# ADCMultiplexerFrontEnd.net
KiCad netlist of a schematic drawn in Altium Designer
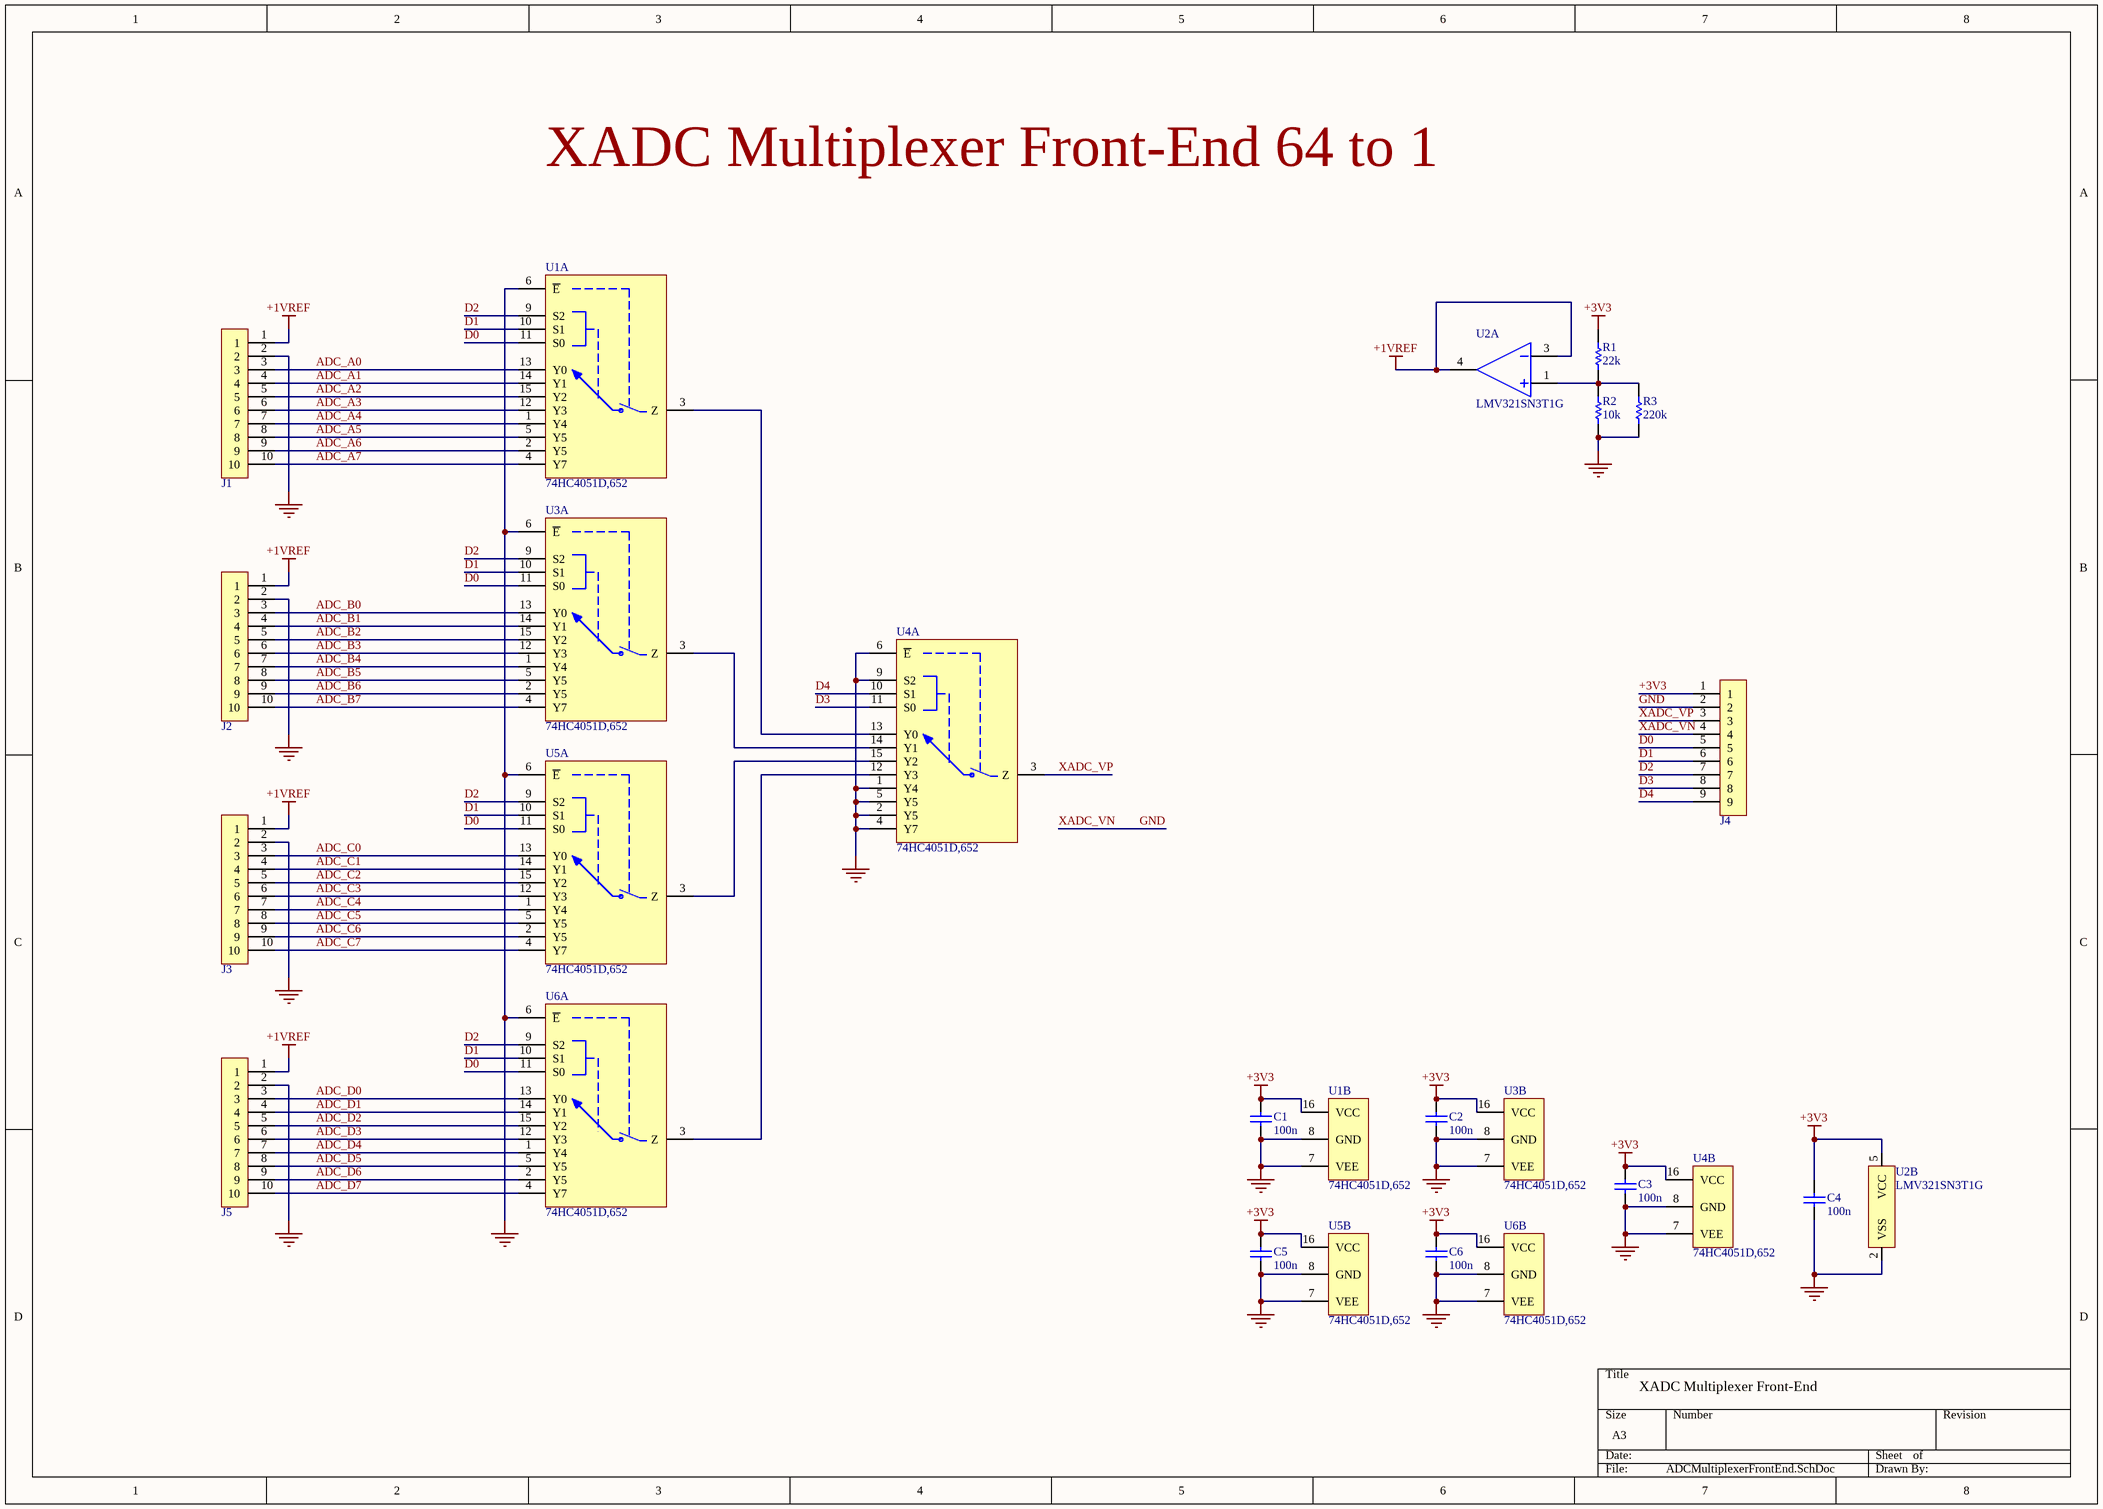
[diagram p0: ADCMultiplexerFrontEnd.SchDoc]

(export (version "E")
  (design (tool "Eeschema 10.0.6"))
  (components
    (comp (ref "C1")
      (value "100n")
      (footprint "C0603")
      (libsource (lib "UserLibrary") (part "C0603KC0G100V104"))
    )
    (comp (ref "C2")
      (value "100n")
      (footprint "C0603")
      (libsource (lib "UserLibrary") (part "C0603KC0G100V104"))
    )
    (comp (ref "C3")
      (value "100n")
      (footprint "C0603")
      (libsource (lib "UserLibrary") (part "C0603KC0G100V104"))
    )
    (comp (ref "C4")
      (value "100n")
      (footprint "C0603")
      (libsource (lib "UserLibrary") (part "C0603KC0G100V104"))
    )
    (comp (ref "C5")
      (value "100n")
      (footprint "C0603")
      (libsource (lib "UserLibrary") (part "C0603KC0G100V104"))
    )
    (comp (ref "C6")
      (value "100n")
      (footprint "C0603")
      (libsource (lib "UserLibrary") (part "C0603KC0G100V104"))
    )
    (comp (ref "J1")
      (value "HDR M 1x8 2.54MM")
      (footprint "HDR M 1x10 2.54MM")
      (libsource (lib "UserLibrary") (part "HDR M 1x10 2.54MM"))
    )
    (comp (ref "J2")
      (value "HDR M 1x8 2.54MM")
      (footprint "HDR M 1x10 2.54MM")
      (libsource (lib "UserLibrary") (part "HDR M 1x10 2.54MM"))
    )
    (comp (ref "J3")
      (value "HDR M 1x8 2.54MM")
      (footprint "HDR M 1x10 2.54MM")
      (libsource (lib "UserLibrary") (part "HDR M 1x10 2.54MM"))
    )
    (comp (ref "J4")
      (value "HDR M 1x8 2.54MM")
      (footprint "HDR M 1x9 2.54MM")
      (libsource (lib "UserLibrary") (part "HDR M 1x9 2.54MM"))
    )
    (comp (ref "J5")
      (value "HDR M 1x8 2.54MM")
      (footprint "HDR M 1x10 2.54MM")
      (libsource (lib "UserLibrary") (part "HDR M 1x10 2.54MM"))
    )
    (comp (ref "R1") (value "22k") (footprint "R0805") (libsource (lib "UserLibrary") (part "R0805F22K")))
    (comp (ref "R2") (value "10k") (footprint "R0805") (libsource (lib "UserLibrary") (part "R0805F10K")))
    (comp (ref "R3") (value "220k") (footprint "R0805") (libsource (lib "UserLibrary") (part "R0805F220K")))
    (comp (ref "U1")
      (value "74HC4051D,652")
      (footprint "SOIC16")
      (description "IC MUX/DEMUX 8X1 16SOIC")
      (fields (field (name "MANUFACTURER") "Nexperia"))
      (libsource (lib "UserLibrary") (part "74HC4051D,652"))
    )
    (comp (ref "U2")
      (value "LMV321SN3T1G")
      (footprint "TSOP5")
      (description "ON SEMICONDUCTOR - LMV321SN3T1G - OP-AMP, SINGLE, 1MHZ, 1V/US, TSOP-5")
      (fields (field (name "MANUFACTURER") "ON Semiconductor"))
      (libsource (lib "") (part "LMV321SN3T1G_1"))
    )
    (comp (ref "U3")
      (value "74HC4051D,652")
      (footprint "SOIC16")
      (description "IC MUX/DEMUX 8X1 16SOIC")
      (fields (field (name "MANUFACTURER") "Nexperia"))
      (libsource (lib "UserLibrary") (part "74HC4051D,652"))
    )
    (comp (ref "U4")
      (value "74HC4051D,652")
      (footprint "SOIC16")
      (description "IC MUX/DEMUX 8X1 16SOIC")
      (fields (field (name "MANUFACTURER") "Nexperia"))
      (libsource (lib "UserLibrary") (part "74HC4051D,652"))
    )
    (comp (ref "U5")
      (value "74HC4051D,652")
      (footprint "SOIC16")
      (description "IC MUX/DEMUX 8X1 16SOIC")
      (fields (field (name "MANUFACTURER") "Nexperia"))
      (libsource (lib "UserLibrary") (part "74HC4051D,652"))
    )
    (comp (ref "U6")
      (value "74HC4051D,652")
      (footprint "SOIC16")
      (description "IC MUX/DEMUX 8X1 16SOIC")
      (fields (field (name "MANUFACTURER") "Nexperia"))
      (libsource (lib "UserLibrary") (part "74HC4051D,652"))
    )
  )
  (nets
    (net (code "1") (name "+1VREF") (class "Default")
      (node (ref "J1") (pin "1") (pinfunction "1_1") (pintype "passive"))
      (node (ref "J2") (pin "1") (pinfunction "1_1") (pintype "passive"))
      (node (ref "J3") (pin "1") (pinfunction "1_1") (pintype "passive"))
      (node (ref "J5") (pin "1") (pinfunction "1_1") (pintype "passive"))
      (node (ref "U2") (pin "3") (pinfunction "3_3") (pintype "passive"))
      (node (ref "U2") (pin "4") (pinfunction "4_4") (pintype "passive"))
    )
    (net (code "2") (name "+3V3") (class "Default")
      (node (ref "C1") (pin "2") (pinfunction "2_2") (pintype "passive"))
      (node (ref "C2") (pin "2") (pinfunction "2_2") (pintype "passive"))
      (node (ref "C3") (pin "2") (pinfunction "2_2") (pintype "passive"))
      (node (ref "C4") (pin "2") (pinfunction "2_2") (pintype "passive"))
      (node (ref "C5") (pin "2") (pinfunction "2_2") (pintype "passive"))
      (node (ref "C6") (pin "2") (pinfunction "2_2") (pintype "passive"))
      (node (ref "J4") (pin "1") (pinfunction "1_1") (pintype "passive"))
      (node (ref "R1") (pin "2") (pinfunction "2_2") (pintype "passive"))
      (node (ref "U1") (pin "16") (pinfunction "VCC_16") (pintype "passive"))
      (node (ref "U2") (pin "5") (pinfunction "VCC_5") (pintype "passive"))
      (node (ref "U3") (pin "16") (pinfunction "VCC_16") (pintype "passive"))
      (node (ref "U4") (pin "16") (pinfunction "VCC_16") (pintype "passive"))
      (node (ref "U5") (pin "16") (pinfunction "VCC_16") (pintype "passive"))
      (node (ref "U6") (pin "16") (pinfunction "VCC_16") (pintype "passive"))
    )
    (net (code "3") (name "/ADC_A0") (class "Default")
      (node (ref "J1") (pin "3") (pinfunction "3_3") (pintype "passive"))
      (node (ref "U1") (pin "13") (pinfunction "Y0_13") (pintype "passive"))
    )
    (net (code "4") (name "/ADC_A1") (class "Default")
      (node (ref "J1") (pin "4") (pinfunction "4_4") (pintype "passive"))
      (node (ref "U1") (pin "14") (pinfunction "Y1_14") (pintype "passive"))
    )
    (net (code "5") (name "/ADC_A2") (class "Default")
      (node (ref "J1") (pin "5") (pinfunction "5_5") (pintype "passive"))
      (node (ref "U1") (pin "15") (pinfunction "Y2_15") (pintype "passive"))
    )
    (net (code "6") (name "/ADC_A3") (class "Default")
      (node (ref "J1") (pin "6") (pinfunction "6_6") (pintype "passive"))
      (node (ref "U1") (pin "12") (pinfunction "Y3_12") (pintype "passive"))
    )
    (net (code "7") (name "/ADC_A4") (class "Default")
      (node (ref "J1") (pin "7") (pinfunction "7_7") (pintype "passive"))
      (node (ref "U1") (pin "1") (pinfunction "Y4_1") (pintype "passive"))
    )
    (net (code "8") (name "/ADC_A5") (class "Default")
      (node (ref "J1") (pin "8") (pinfunction "8_8") (pintype "passive"))
      (node (ref "U1") (pin "5") (pinfunction "Y5_5") (pintype "passive"))
    )
    (net (code "9") (name "/ADC_A6") (class "Default")
      (node (ref "J1") (pin "9") (pinfunction "9_9") (pintype "passive"))
      (node (ref "U1") (pin "2") (pinfunction "Y5_2") (pintype "passive"))
    )
    (net (code "10") (name "/ADC_A7") (class "Default")
      (node (ref "J1") (pin "10") (pinfunction "10_10") (pintype "passive"))
      (node (ref "U1") (pin "4") (pinfunction "Y7_4") (pintype "passive"))
    )
    (net (code "11") (name "/ADC_B0") (class "Default")
      (node (ref "J2") (pin "3") (pinfunction "3_3") (pintype "passive"))
      (node (ref "U3") (pin "13") (pinfunction "Y0_13") (pintype "passive"))
    )
    (net (code "12") (name "/ADC_B1") (class "Default")
      (node (ref "J2") (pin "4") (pinfunction "4_4") (pintype "passive"))
      (node (ref "U3") (pin "14") (pinfunction "Y1_14") (pintype "passive"))
    )
    (net (code "13") (name "/ADC_B2") (class "Default")
      (node (ref "J2") (pin "5") (pinfunction "5_5") (pintype "passive"))
      (node (ref "U3") (pin "15") (pinfunction "Y2_15") (pintype "passive"))
    )
    (net (code "14") (name "/ADC_B3") (class "Default")
      (node (ref "J2") (pin "6") (pinfunction "6_6") (pintype "passive"))
      (node (ref "U3") (pin "12") (pinfunction "Y3_12") (pintype "passive"))
    )
    (net (code "15") (name "/ADC_B4") (class "Default")
      (node (ref "J2") (pin "7") (pinfunction "7_7") (pintype "passive"))
      (node (ref "U3") (pin "1") (pinfunction "Y4_1") (pintype "passive"))
    )
    (net (code "16") (name "/ADC_B5") (class "Default")
      (node (ref "J2") (pin "8") (pinfunction "8_8") (pintype "passive"))
      (node (ref "U3") (pin "5") (pinfunction "Y5_5") (pintype "passive"))
    )
    (net (code "17") (name "/ADC_B6") (class "Default")
      (node (ref "J2") (pin "9") (pinfunction "9_9") (pintype "passive"))
      (node (ref "U3") (pin "2") (pinfunction "Y5_2") (pintype "passive"))
    )
    (net (code "18") (name "/ADC_B7") (class "Default")
      (node (ref "J2") (pin "10") (pinfunction "10_10") (pintype "passive"))
      (node (ref "U3") (pin "4") (pinfunction "Y7_4") (pintype "passive"))
    )
    (net (code "19") (name "/ADC_C0") (class "Default")
      (node (ref "J3") (pin "3") (pinfunction "3_3") (pintype "passive"))
      (node (ref "U5") (pin "13") (pinfunction "Y0_13") (pintype "passive"))
    )
    (net (code "20") (name "/ADC_C1") (class "Default")
      (node (ref "J3") (pin "4") (pinfunction "4_4") (pintype "passive"))
      (node (ref "U5") (pin "14") (pinfunction "Y1_14") (pintype "passive"))
    )
    (net (code "21") (name "/ADC_C2") (class "Default")
      (node (ref "J3") (pin "5") (pinfunction "5_5") (pintype "passive"))
      (node (ref "U5") (pin "15") (pinfunction "Y2_15") (pintype "passive"))
    )
    (net (code "22") (name "/ADC_C3") (class "Default")
      (node (ref "J3") (pin "6") (pinfunction "6_6") (pintype "passive"))
      (node (ref "U5") (pin "12") (pinfunction "Y3_12") (pintype "passive"))
    )
    (net (code "23") (name "/ADC_C4") (class "Default")
      (node (ref "J3") (pin "7") (pinfunction "7_7") (pintype "passive"))
      (node (ref "U5") (pin "1") (pinfunction "Y4_1") (pintype "passive"))
    )
    (net (code "24") (name "/ADC_C5") (class "Default")
      (node (ref "J3") (pin "8") (pinfunction "8_8") (pintype "passive"))
      (node (ref "U5") (pin "5") (pinfunction "Y5_5") (pintype "passive"))
    )
    (net (code "25") (name "/ADC_C6") (class "Default")
      (node (ref "J3") (pin "9") (pinfunction "9_9") (pintype "passive"))
      (node (ref "U5") (pin "2") (pinfunction "Y5_2") (pintype "passive"))
    )
    (net (code "26") (name "/ADC_C7") (class "Default")
      (node (ref "J3") (pin "10") (pinfunction "10_10") (pintype "passive"))
      (node (ref "U5") (pin "4") (pinfunction "Y7_4") (pintype "passive"))
    )
    (net (code "27") (name "/ADC_D0") (class "Default")
      (node (ref "J5") (pin "3") (pinfunction "3_3") (pintype "passive"))
      (node (ref "U6") (pin "13") (pinfunction "Y0_13") (pintype "passive"))
    )
    (net (code "28") (name "/ADC_D1") (class "Default")
      (node (ref "J5") (pin "4") (pinfunction "4_4") (pintype "passive"))
      (node (ref "U6") (pin "14") (pinfunction "Y1_14") (pintype "passive"))
    )
    (net (code "29") (name "/ADC_D2") (class "Default")
      (node (ref "J5") (pin "5") (pinfunction "5_5") (pintype "passive"))
      (node (ref "U6") (pin "15") (pinfunction "Y2_15") (pintype "passive"))
    )
    (net (code "30") (name "/ADC_D3") (class "Default")
      (node (ref "J5") (pin "6") (pinfunction "6_6") (pintype "passive"))
      (node (ref "U6") (pin "12") (pinfunction "Y3_12") (pintype "passive"))
    )
    (net (code "31") (name "/ADC_D4") (class "Default")
      (node (ref "J5") (pin "7") (pinfunction "7_7") (pintype "passive"))
      (node (ref "U6") (pin "1") (pinfunction "Y4_1") (pintype "passive"))
    )
    (net (code "32") (name "/ADC_D5") (class "Default")
      (node (ref "J5") (pin "8") (pinfunction "8_8") (pintype "passive"))
      (node (ref "U6") (pin "5") (pinfunction "Y5_5") (pintype "passive"))
    )
    (net (code "33") (name "/ADC_D6") (class "Default")
      (node (ref "J5") (pin "9") (pinfunction "9_9") (pintype "passive"))
      (node (ref "U6") (pin "2") (pinfunction "Y5_2") (pintype "passive"))
    )
    (net (code "34") (name "/ADC_D7") (class "Default")
      (node (ref "J5") (pin "10") (pinfunction "10_10") (pintype "passive"))
      (node (ref "U6") (pin "4") (pinfunction "Y7_4") (pintype "passive"))
    )
    (net (code "35") (name "/D0") (class "Default")
      (node (ref "J4") (pin "5") (pinfunction "5_5") (pintype "passive"))
      (node (ref "U1") (pin "11") (pinfunction "S0_11") (pintype "passive"))
      (node (ref "U3") (pin "11") (pinfunction "S0_11") (pintype "passive"))
      (node (ref "U5") (pin "11") (pinfunction "S0_11") (pintype "passive"))
      (node (ref "U6") (pin "11") (pinfunction "S0_11") (pintype "passive"))
    )
    (net (code "36") (name "/D1") (class "Default")
      (node (ref "J4") (pin "6") (pinfunction "6_6") (pintype "passive"))
      (node (ref "U1") (pin "10") (pinfunction "S1_10") (pintype "passive"))
      (node (ref "U3") (pin "10") (pinfunction "S1_10") (pintype "passive"))
      (node (ref "U5") (pin "10") (pinfunction "S1_10") (pintype "passive"))
      (node (ref "U6") (pin "10") (pinfunction "S1_10") (pintype "passive"))
    )
    (net (code "37") (name "/D2") (class "Default")
      (node (ref "J4") (pin "7") (pinfunction "7_7") (pintype "passive"))
      (node (ref "U1") (pin "9") (pinfunction "S2_9") (pintype "passive"))
      (node (ref "U3") (pin "9") (pinfunction "S2_9") (pintype "passive"))
      (node (ref "U5") (pin "9") (pinfunction "S2_9") (pintype "passive"))
      (node (ref "U6") (pin "9") (pinfunction "S2_9") (pintype "passive"))
    )
    (net (code "38") (name "/D3") (class "Default")
      (node (ref "J4") (pin "8") (pinfunction "8_8") (pintype "passive"))
      (node (ref "U4") (pin "11") (pinfunction "S0_11") (pintype "passive"))
    )
    (net (code "39") (name "/D4") (class "Default")
      (node (ref "J4") (pin "9") (pinfunction "9_9") (pintype "passive"))
      (node (ref "U4") (pin "10") (pinfunction "S1_10") (pintype "passive"))
    )
    (net (code "40") (name "/XADC_VP") (class "Default")
      (node (ref "J4") (pin "3") (pinfunction "3_3") (pintype "passive"))
      (node (ref "U4") (pin "3") (pinfunction "Z_3") (pintype "passive"))
    )
    (net (code "41") (name "GND") (class "Default")
      (node (ref "C1") (pin "1") (pinfunction "1_1") (pintype "passive"))
      (node (ref "C2") (pin "1") (pinfunction "1_1") (pintype "passive"))
      (node (ref "C3") (pin "1") (pinfunction "1_1") (pintype "passive"))
      (node (ref "C4") (pin "1") (pinfunction "1_1") (pintype "passive"))
      (node (ref "C5") (pin "1") (pinfunction "1_1") (pintype "passive"))
      (node (ref "C6") (pin "1") (pinfunction "1_1") (pintype "passive"))
      (node (ref "J1") (pin "2") (pinfunction "2_2") (pintype "passive"))
      (node (ref "J2") (pin "2") (pinfunction "2_2") (pintype "passive"))
      (node (ref "J3") (pin "2") (pinfunction "2_2") (pintype "passive"))
      (node (ref "J4") (pin "2") (pinfunction "2_2") (pintype "passive"))
      (node (ref "J4") (pin "4") (pinfunction "4_4") (pintype "passive"))
      (node (ref "J5") (pin "2") (pinfunction "2_2") (pintype "passive"))
      (node (ref "R2") (pin "1") (pinfunction "1_1") (pintype "passive"))
      (node (ref "R3") (pin "1") (pinfunction "1_1") (pintype "passive"))
      (node (ref "U1") (pin "6") (pinfunction "~{E}_6") (pintype "passive"))
      (node (ref "U1") (pin "7") (pinfunction "VEE_7") (pintype "passive"))
      (node (ref "U1") (pin "8") (pinfunction "GND_8") (pintype "passive"))
      (node (ref "U2") (pin "2") (pinfunction "VSS_2") (pintype "passive"))
      (node (ref "U3") (pin "6") (pinfunction "~{E}_6") (pintype "passive"))
      (node (ref "U3") (pin "7") (pinfunction "VEE_7") (pintype "passive"))
      (node (ref "U3") (pin "8") (pinfunction "GND_8") (pintype "passive"))
      (node (ref "U4") (pin "1") (pinfunction "Y4_1") (pintype "passive"))
      (node (ref "U4") (pin "2") (pinfunction "Y5_2") (pintype "passive"))
      (node (ref "U4") (pin "4") (pinfunction "Y7_4") (pintype "passive"))
      (node (ref "U4") (pin "5") (pinfunction "Y5_5") (pintype "passive"))
      (node (ref "U4") (pin "6") (pinfunction "~{E}_6") (pintype "passive"))
      (node (ref "U4") (pin "7") (pinfunction "VEE_7") (pintype "passive"))
      (node (ref "U4") (pin "8") (pinfunction "GND_8") (pintype "passive"))
      (node (ref "U4") (pin "9") (pinfunction "S2_9") (pintype "passive"))
      (node (ref "U5") (pin "6") (pinfunction "~{E}_6") (pintype "passive"))
      (node (ref "U5") (pin "7") (pinfunction "VEE_7") (pintype "passive"))
      (node (ref "U5") (pin "8") (pinfunction "GND_8") (pintype "passive"))
      (node (ref "U6") (pin "6") (pinfunction "~{E}_6") (pintype "passive"))
      (node (ref "U6") (pin "7") (pinfunction "VEE_7") (pintype "passive"))
      (node (ref "U6") (pin "8") (pinfunction "GND_8") (pintype "passive"))
    )
    (net (code "42") (name "Net-(R1-Pad1)") (class "Default")
      (node (ref "R1") (pin "1") (pinfunction "1_1") (pintype "passive"))
      (node (ref "R2") (pin "2") (pinfunction "2_2") (pintype "passive"))
      (node (ref "R3") (pin "2") (pinfunction "2_2") (pintype "passive"))
      (node (ref "U2") (pin "1") (pinfunction "1_1") (pintype "passive"))
    )
    (net (code "43") (name "Net-(U1A-Z)") (class "Default")
      (node (ref "U1") (pin "3") (pinfunction "Z_3") (pintype "passive"))
      (node (ref "U4") (pin "13") (pinfunction "Y0_13") (pintype "passive"))
    )
    (net (code "44") (name "Net-(U3A-Z)") (class "Default")
      (node (ref "U3") (pin "3") (pinfunction "Z_3") (pintype "passive"))
      (node (ref "U4") (pin "14") (pinfunction "Y1_14") (pintype "passive"))
    )
    (net (code "45") (name "Net-(U4A-Y2)") (class "Default")
      (node (ref "U4") (pin "15") (pinfunction "Y2_15") (pintype "passive"))
      (node (ref "U5") (pin "3") (pinfunction "Z_3") (pintype "passive"))
    )
    (net (code "46") (name "Net-(U4A-Y3)") (class "Default")
      (node (ref "U4") (pin "12") (pinfunction "Y3_12") (pintype "passive"))
      (node (ref "U6") (pin "3") (pinfunction "Z_3") (pintype "passive"))
    )
  )
)
